# rev1.net
KiCad netlist of a schematic drawn in EAGLE
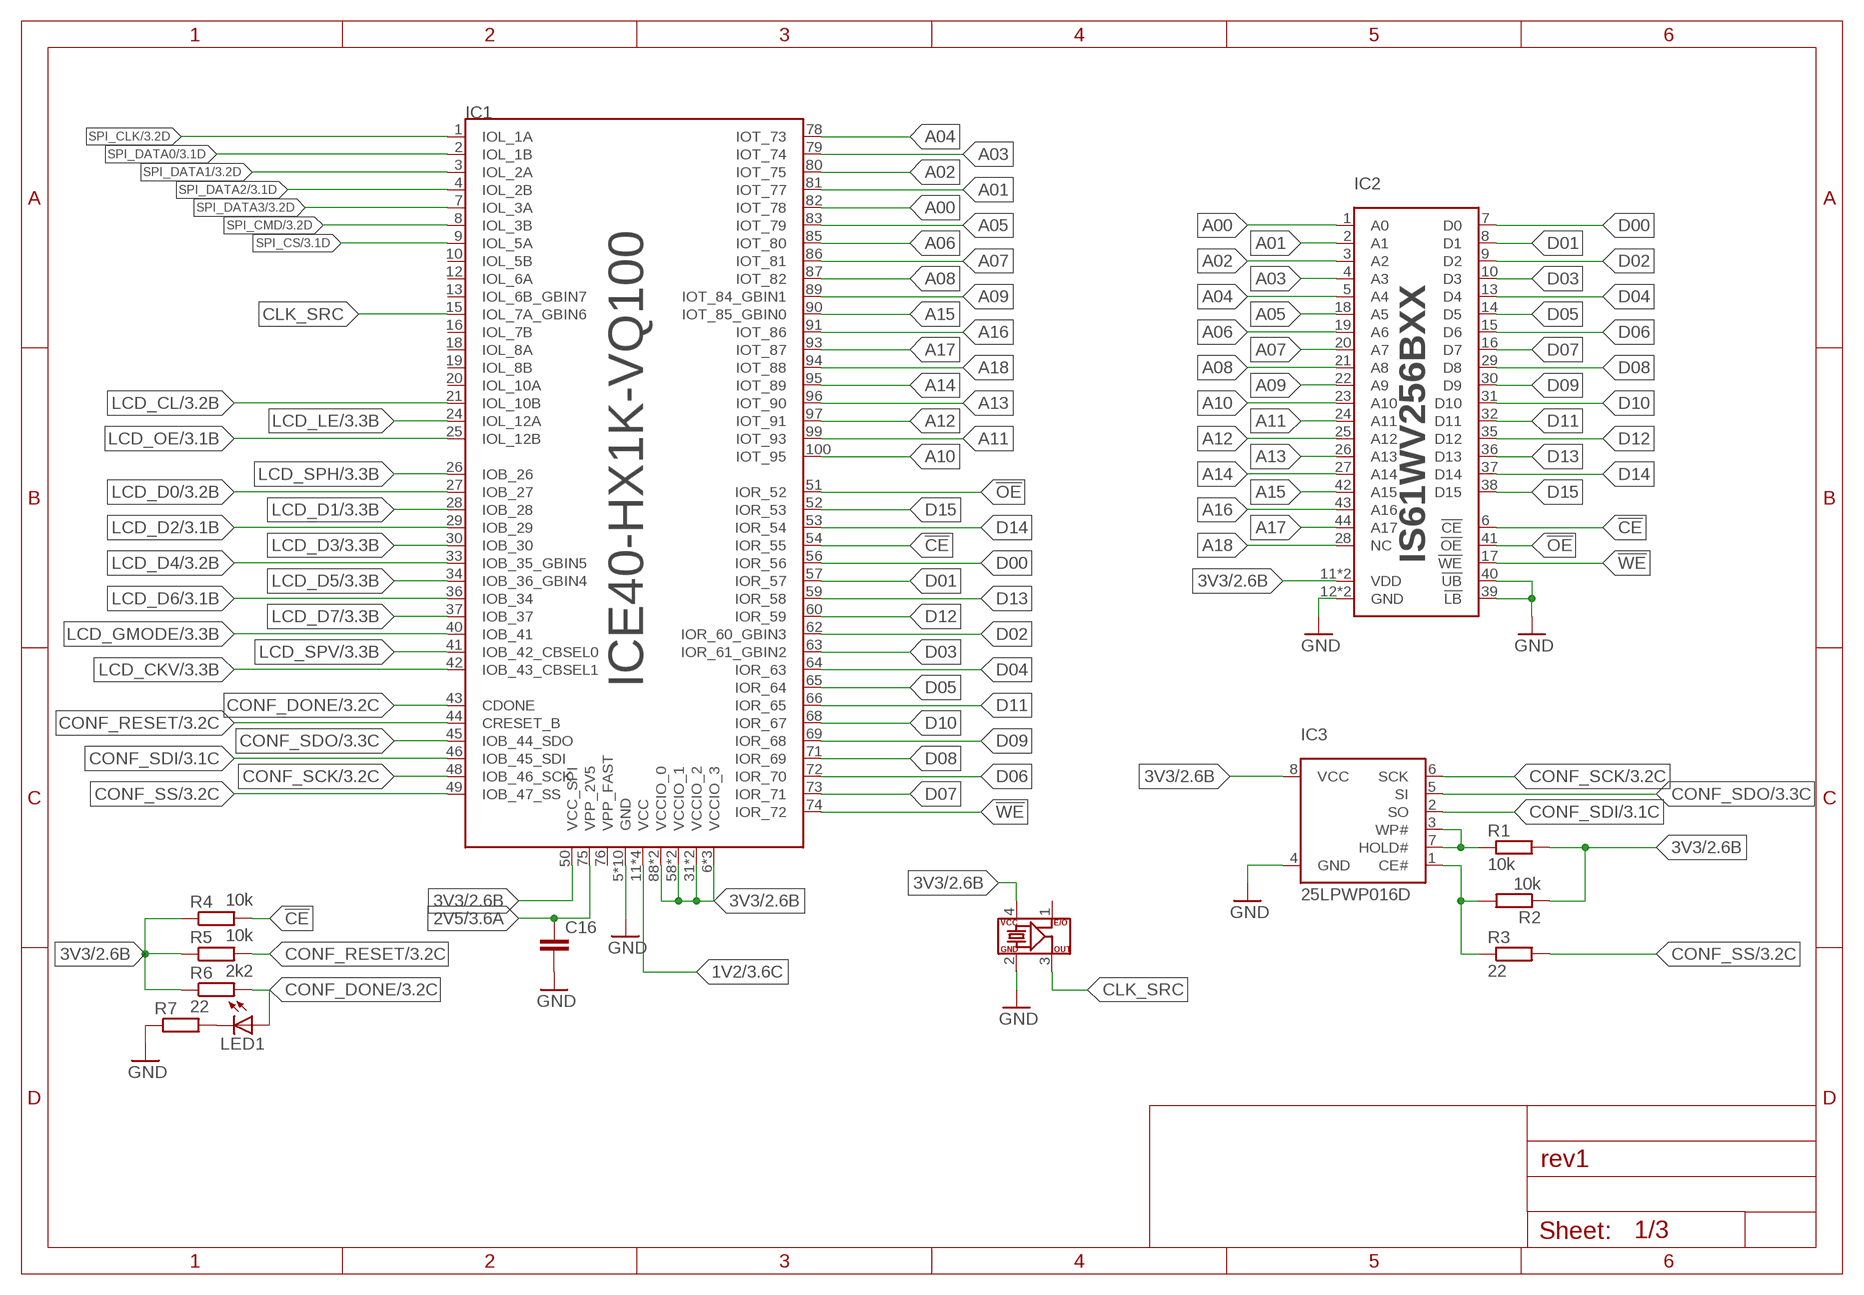
[diagram p0: schematic, sheet 1]
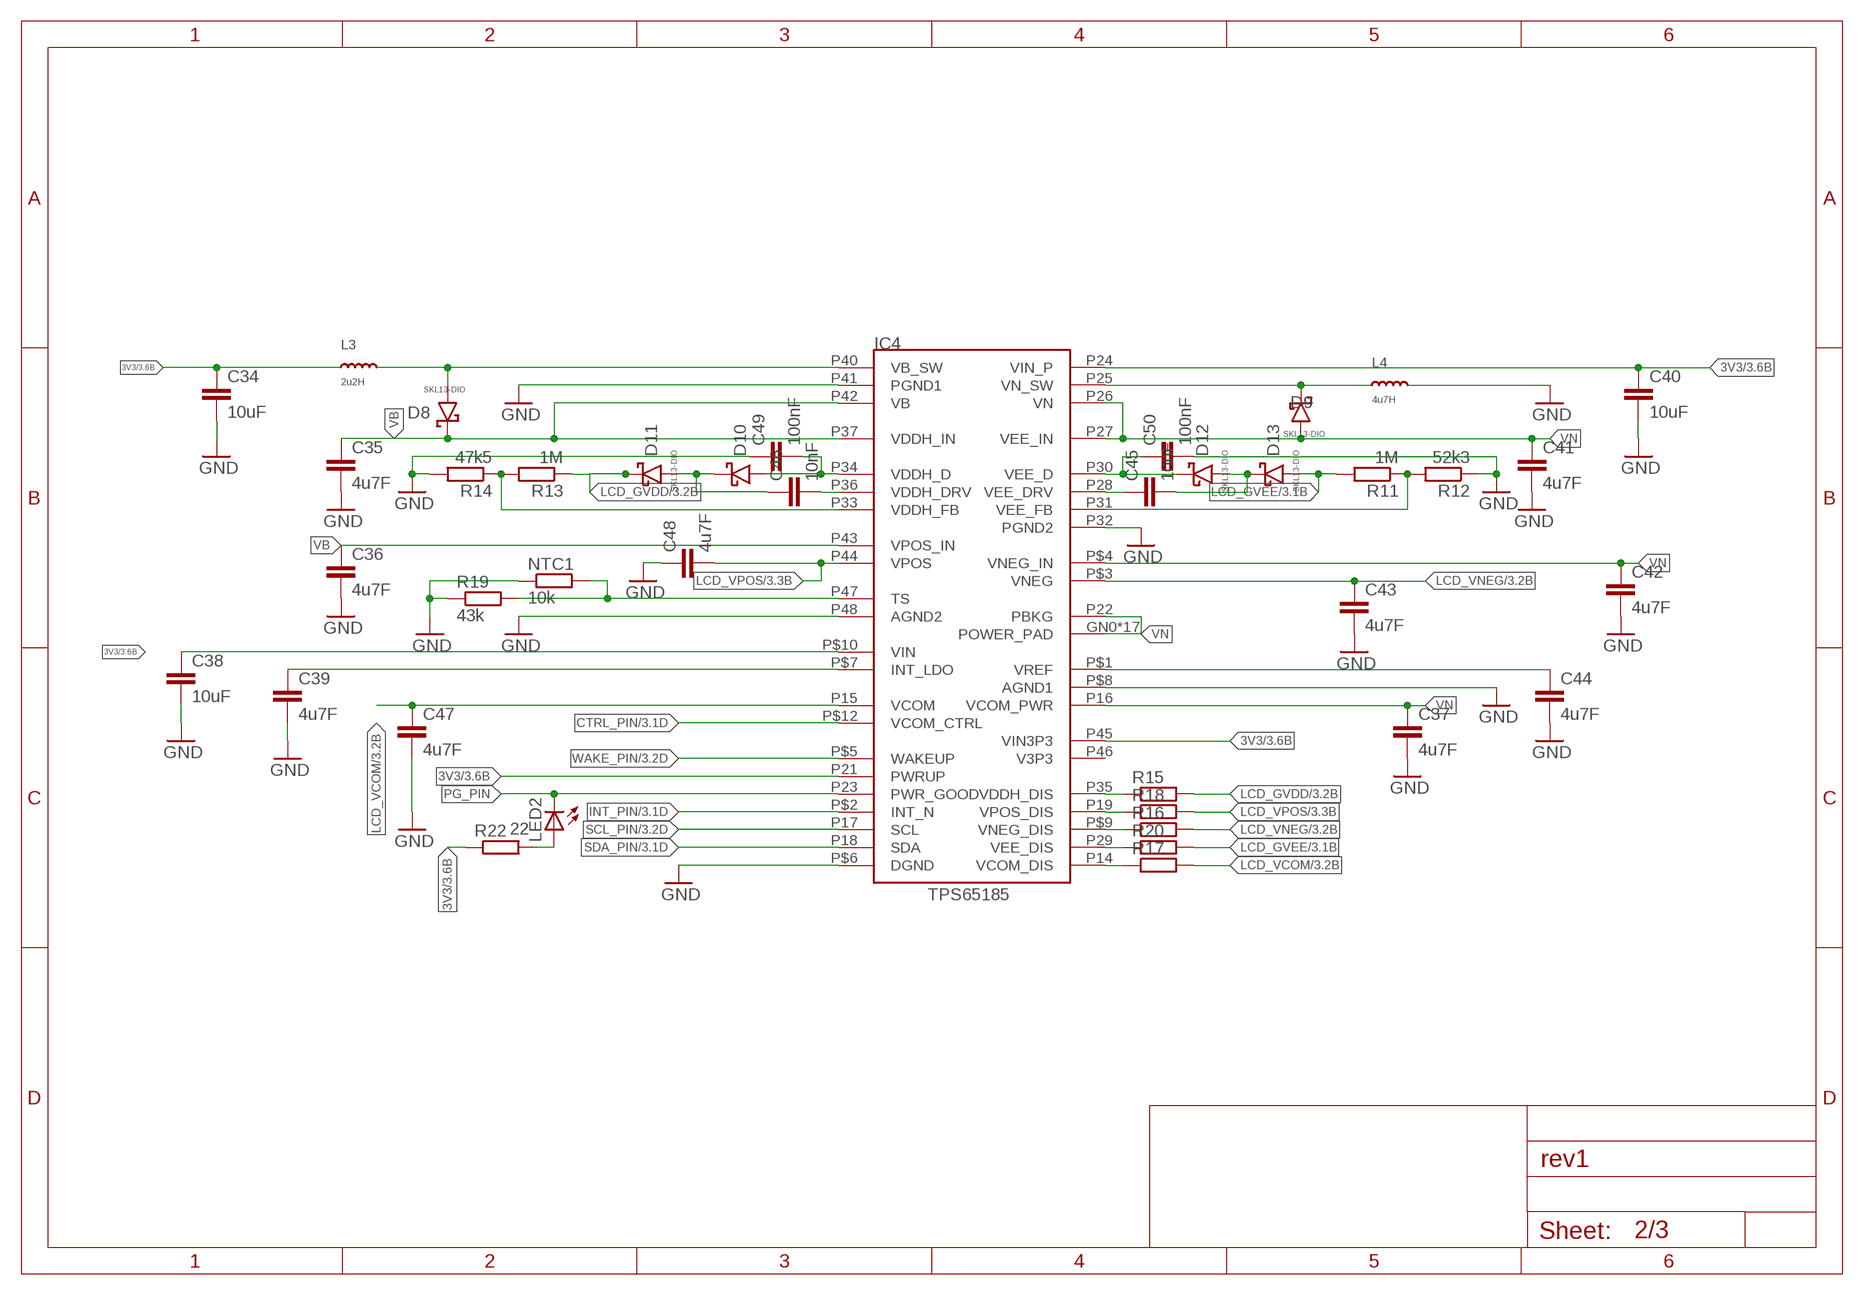
[diagram p1: schematic, sheet 2]
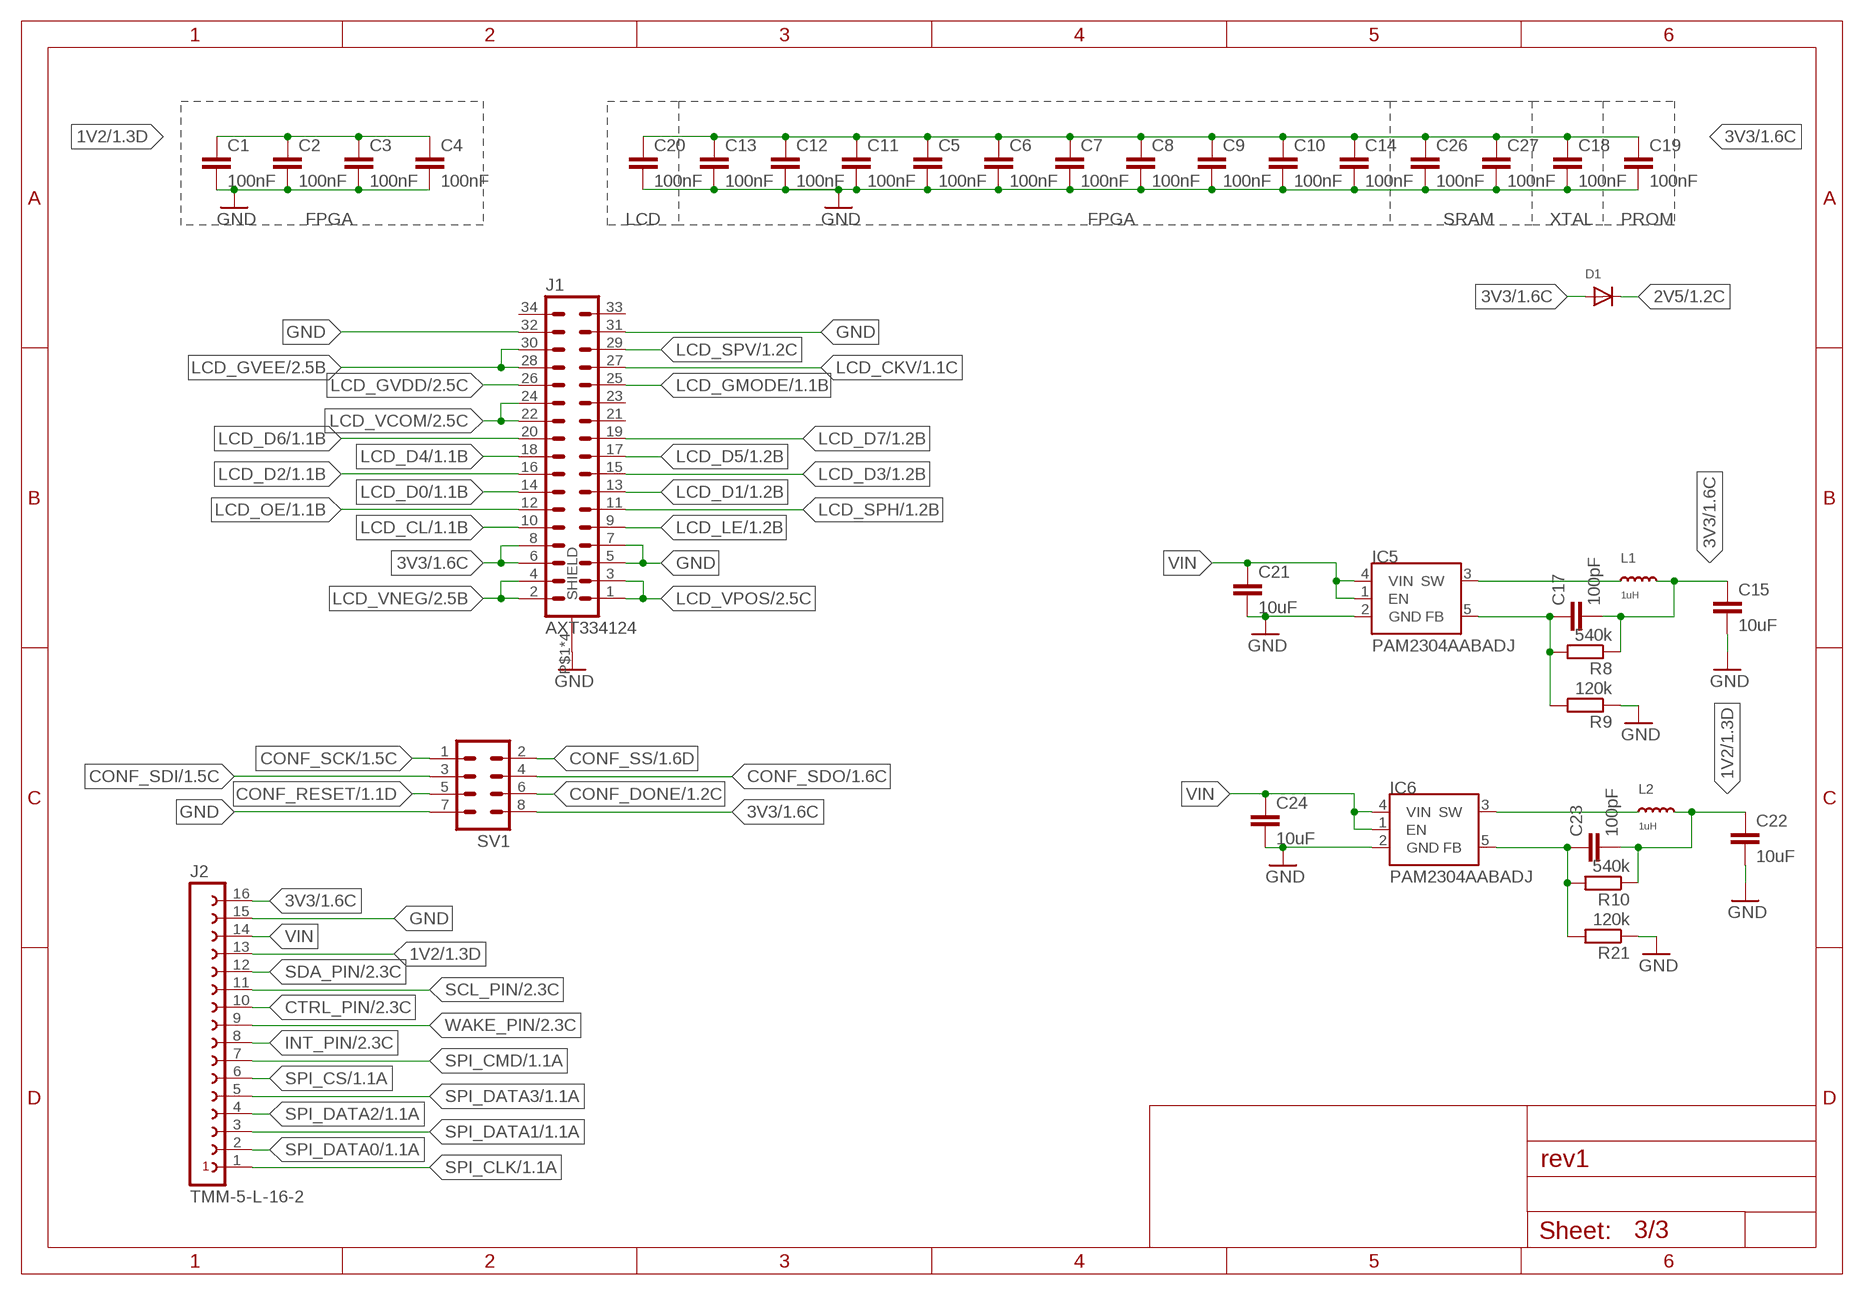
[diagram p2: schematic, sheet 3]

(export (version "E")
  (design (tool "Eeschema 10.0.6"))
  (components
    (comp (ref "C34")
      (value "10uF")
      (footprint "eagle-import:C0805")
      (libsource (lib "eagle-import") (part "C-EUC0805"))
    )
    (comp (ref "C35")
      (value "4u7F")
      (footprint "eagle-import:C0805")
      (libsource (lib "eagle-import") (part "C-EUC0805"))
    )
    (comp (ref "C36")
      (value "4u7F")
      (footprint "eagle-import:C0805")
      (libsource (lib "eagle-import") (part "C-EUC0805"))
    )
    (comp (ref "C37")
      (value "4u7F")
      (footprint "eagle-import:C0805")
      (libsource (lib "eagle-import") (part "C-EUC0805"))
    )
    (comp (ref "C38")
      (value "10uF")
      (footprint "eagle-import:C0805")
      (libsource (lib "eagle-import") (part "C-EUC0805"))
    )
    (comp (ref "C39")
      (value "4u7F")
      (footprint "eagle-import:C0603")
      (libsource (lib "eagle-import") (part "C-EUC0603"))
    )
    (comp (ref "C40")
      (value "10uF")
      (footprint "eagle-import:C0805")
      (libsource (lib "eagle-import") (part "C-EUC0805"))
    )
    (comp (ref "C41")
      (value "4u7F")
      (footprint "eagle-import:C0805")
      (libsource (lib "eagle-import") (part "C-EUC0805"))
    )
    (comp (ref "C42")
      (value "4u7F")
      (footprint "eagle-import:C0805")
      (libsource (lib "eagle-import") (part "C-EUC0805"))
    )
    (comp (ref "C43")
      (value "4u7F")
      (footprint "eagle-import:C0805")
      (libsource (lib "eagle-import") (part "C-EUC0805"))
    )
    (comp (ref "C44")
      (value "4u7F")
      (footprint "eagle-import:C0603")
      (libsource (lib "eagle-import") (part "C-EUC0603"))
    )
    (comp (ref "C45")
      (value "10nF")
      (footprint "eagle-import:C0402")
      (libsource (lib "eagle-import") (part "C-EUC0402"))
    )
    (comp (ref "C46")
      (value "10nF")
      (footprint "eagle-import:C0402")
      (libsource (lib "eagle-import") (part "C-EUC0402"))
    )
    (comp (ref "C47")
      (value "4u7F")
      (footprint "eagle-import:C0603")
      (libsource (lib "eagle-import") (part "C-EUC0603"))
    )
    (comp (ref "C48")
      (value "4u7F")
      (footprint "eagle-import:C0805")
      (libsource (lib "eagle-import") (part "C-EUC0805"))
    )
    (comp (ref "C49")
      (value "100nF")
      (footprint "eagle-import:C0402")
      (libsource (lib "eagle-import") (part "C-EUC0402"))
    )
    (comp (ref "C50")
      (value "100nF")
      (footprint "eagle-import:C0402")
      (libsource (lib "eagle-import") (part "C-EUC0402"))
    )
    (comp (ref "D8")
      (value "SKL13-DIO")
      (footprint "eagle-import:SOD523")
      (libsource (lib "eagle-import") (part "RB520S30T"))
    )
    (comp (ref "D9")
      (value "SKL13-DIO")
      (footprint "eagle-import:SOD523")
      (libsource (lib "eagle-import") (part "RB520S30T"))
    )
    (comp (ref "D10")
      (value "SKL13-DIO")
      (footprint "eagle-import:SOD523")
      (libsource (lib "eagle-import") (part "RB520S30T"))
    )
    (comp (ref "D11")
      (value "SKL13-DIO")
      (footprint "eagle-import:SOD523")
      (libsource (lib "eagle-import") (part "RB520S30T"))
    )
    (comp (ref "D12")
      (value "SKL13-DIO")
      (footprint "eagle-import:SOD523")
      (libsource (lib "eagle-import") (part "RB520S30T"))
    )
    (comp (ref "D13")
      (value "SKL13-DIO")
      (footprint "eagle-import:SOD523")
      (libsource (lib "eagle-import") (part "RB520S30T"))
    )
    (comp (ref "IC4")
      (value "TPS65185")
      (footprint "eagle-import:RGZ")
      (libsource (lib "eagle-import") (part "TPS65185"))
    )
    (comp (ref "L3")
      (value "2u2H")
      (footprint "eagle-import:3015")
      (libsource (lib "eagle-import") (part "DJNR-3015-2R2"))
    )
    (comp (ref "L4")
      (value "4u7H")
      (footprint "eagle-import:3015")
      (libsource (lib "eagle-import") (part "DJNR-3015-1R0"))
    )
    (comp (ref "LED2")
      (value "LEDCHIP-LED0603")
      (footprint "eagle-import:CHIP-LED0603")
      (libsource (lib "eagle-import") (part "LEDCHIP-LED0603"))
    )
    (comp (ref "NTC1")
      (value "10k")
      (footprint "eagle-import:R0603")
      (libsource (lib "eagle-import") (part "R-EU_R0603"))
    )
    (comp (ref "R11")
      (value "1M")
      (footprint "eagle-import:R0603")
      (libsource (lib "eagle-import") (part "R-EU_R0603"))
    )
    (comp (ref "R12")
      (value "52k3")
      (footprint "eagle-import:R0603")
      (libsource (lib "eagle-import") (part "R-EU_R0603"))
    )
    (comp (ref "R13")
      (value "1M")
      (footprint "eagle-import:R0603")
      (libsource (lib "eagle-import") (part "R-EU_R0603"))
    )
    (comp (ref "R14")
      (value "47k5")
      (footprint "eagle-import:R0603")
      (libsource (lib "eagle-import") (part "R-EU_R0603"))
    )
    (comp (ref "R15")
      (value "R-EU_R0603")
      (footprint "eagle-import:R0603")
      (libsource (lib "eagle-import") (part "R-EU_R0603"))
    )
    (comp (ref "R16")
      (value "R-EU_R0603")
      (footprint "eagle-import:R0603")
      (libsource (lib "eagle-import") (part "R-EU_R0603"))
    )
    (comp (ref "R17")
      (value "R-EU_R0603")
      (footprint "eagle-import:R0603")
      (libsource (lib "eagle-import") (part "R-EU_R0603"))
    )
    (comp (ref "R18")
      (value "R-EU_R0603")
      (footprint "eagle-import:R0603")
      (libsource (lib "eagle-import") (part "R-EU_R0603"))
    )
    (comp (ref "R19")
      (value "43k")
      (footprint "eagle-import:R0603")
      (libsource (lib "eagle-import") (part "R-EU_R0603"))
    )
    (comp (ref "R20")
      (value "R-EU_R0603")
      (footprint "eagle-import:R0603")
      (libsource (lib "eagle-import") (part "R-EU_R0603"))
    )
    (comp (ref "R22")
      (value "22")
      (footprint "eagle-import:R0402")
      (libsource (lib "eagle-import") (part "R-EU_R0402"))
    )
    (comp (ref "C1")
      (value "100nF")
      (footprint "eagle-import:C0402")
      (libsource (lib "eagle-import") (part "C-EUC0402"))
    )
    (comp (ref "C2")
      (value "100nF")
      (footprint "eagle-import:C0402")
      (libsource (lib "eagle-import") (part "C-EUC0402"))
    )
    (comp (ref "C3")
      (value "100nF")
      (footprint "eagle-import:C0402")
      (libsource (lib "eagle-import") (part "C-EUC0402"))
    )
    (comp (ref "C4")
      (value "100nF")
      (footprint "eagle-import:C0402")
      (libsource (lib "eagle-import") (part "C-EUC0402"))
    )
    (comp (ref "C5")
      (value "100nF")
      (footprint "eagle-import:C0402")
      (libsource (lib "eagle-import") (part "C-EUC0402"))
    )
    (comp (ref "C6")
      (value "100nF")
      (footprint "eagle-import:C0402")
      (libsource (lib "eagle-import") (part "C-EUC0402"))
    )
    (comp (ref "C7")
      (value "100nF")
      (footprint "eagle-import:C0402")
      (libsource (lib "eagle-import") (part "C-EUC0402"))
    )
    (comp (ref "C8")
      (value "100nF")
      (footprint "eagle-import:C0402")
      (libsource (lib "eagle-import") (part "C-EUC0402"))
    )
    (comp (ref "C9")
      (value "100nF")
      (footprint "eagle-import:C0402")
      (libsource (lib "eagle-import") (part "C-EUC0402"))
    )
    (comp (ref "C10")
      (value "100nF")
      (footprint "eagle-import:C0402")
      (libsource (lib "eagle-import") (part "C-EUC0402"))
    )
    (comp (ref "C11")
      (value "100nF")
      (footprint "eagle-import:C0402")
      (libsource (lib "eagle-import") (part "C-EUC0402"))
    )
    (comp (ref "C12")
      (value "100nF")
      (footprint "eagle-import:C0402")
      (libsource (lib "eagle-import") (part "C-EUC0402"))
    )
    (comp (ref "C13")
      (value "100nF")
      (footprint "eagle-import:C0402")
      (libsource (lib "eagle-import") (part "C-EUC0402"))
    )
    (comp (ref "C14")
      (value "100nF")
      (footprint "eagle-import:C0402")
      (libsource (lib "eagle-import") (part "C-EUC0402"))
    )
    (comp (ref "C15")
      (value "10uF")
      (footprint "eagle-import:C0603")
      (libsource (lib "eagle-import") (part "C-EUC0603"))
    )
    (comp (ref "C17")
      (value "100pF")
      (footprint "eagle-import:C0402")
      (libsource (lib "eagle-import") (part "C-EUC0402"))
    )
    (comp (ref "C18")
      (value "100nF")
      (footprint "eagle-import:C0402")
      (libsource (lib "eagle-import") (part "C-EUC0402"))
    )
    (comp (ref "C19")
      (value "100nF")
      (footprint "eagle-import:C0402")
      (libsource (lib "eagle-import") (part "C-EUC0402"))
    )
    (comp (ref "C20")
      (value "100nF")
      (footprint "eagle-import:C0402")
      (libsource (lib "eagle-import") (part "C-EUC0402"))
    )
    (comp (ref "C21")
      (value "10uF")
      (footprint "eagle-import:C0603")
      (libsource (lib "eagle-import") (part "C-EUC0603"))
    )
    (comp (ref "C22")
      (value "10uF")
      (footprint "eagle-import:C0603")
      (libsource (lib "eagle-import") (part "C-EUC0603"))
    )
    (comp (ref "C23")
      (value "100pF")
      (footprint "eagle-import:C0402")
      (libsource (lib "eagle-import") (part "C-EUC0402"))
    )
    (comp (ref "C24")
      (value "10uF")
      (footprint "eagle-import:C0603")
      (libsource (lib "eagle-import") (part "C-EUC0603"))
    )
    (comp (ref "C26")
      (value "100nF")
      (footprint "eagle-import:C0402")
      (libsource (lib "eagle-import") (part "C-EUC0402"))
    )
    (comp (ref "C27")
      (value "100nF")
      (footprint "eagle-import:C0402")
      (libsource (lib "eagle-import") (part "C-EUC0402"))
    )
    (comp (ref "D1")
      (value "DIODESOD-123")
      (footprint "eagle-import:SOD-123")
      (libsource (lib "eagle-import") (part "DIODESOD-123"))
    )
    (comp (ref "IC5")
      (value "PAM2304AABADJ")
      (footprint "eagle-import:TSOT25")
      (libsource (lib "eagle-import") (part "PAM2304AABADJ"))
    )
    (comp (ref "IC6")
      (value "PAM2304AABADJ")
      (footprint "eagle-import:TSOT25")
      (libsource (lib "eagle-import") (part "PAM2304AABADJ"))
    )
    (comp (ref "J1")
      (value "AXT334124")
      (footprint "eagle-import:AXT334124")
      (libsource (lib "eagle-import") (part "AXT334124"))
    )
    (comp (ref "J2")
      (value "TMM-5-L-16-2")
      (footprint "eagle-import:TMM-5-L-16-2")
      (libsource (lib "eagle-import") (part "TMM-5-L-16-2"))
    )
    (comp (ref "L1")
      (value "1uH")
      (footprint "eagle-import:3015")
      (libsource (lib "eagle-import") (part "DJNR-3015-1R0"))
    )
    (comp (ref "L2")
      (value "1uH")
      (footprint "eagle-import:3015")
      (libsource (lib "eagle-import") (part "DJNR-3015-1R0"))
    )
    (comp (ref "R8")
      (value "540k")
      (footprint "eagle-import:R0402")
      (libsource (lib "eagle-import") (part "R-EU_R0402"))
    )
    (comp (ref "R9")
      (value "120k")
      (footprint "eagle-import:R0402")
      (libsource (lib "eagle-import") (part "R-EU_R0402"))
    )
    (comp (ref "R10")
      (value "540k")
      (footprint "eagle-import:R0402")
      (libsource (lib "eagle-import") (part "R-EU_R0402"))
    )
    (comp (ref "R21")
      (value "120k")
      (footprint "eagle-import:R0402")
      (libsource (lib "eagle-import") (part "R-EU_R0402"))
    )
    (comp (ref "SV1")
      (value "MA04-2")
      (footprint "eagle-import:MA04-2")
      (libsource (lib "eagle-import") (part "MA04-2"))
    )
    (comp (ref "C16")
      (value "C-EUC0402")
      (footprint "eagle-import:C0402")
      (libsource (lib "eagle-import") (part "C-EUC0402"))
    )
    (comp (ref "IC1")
      (value "ICE40-HX1K-VQ100")
      (footprint "eagle-import:VQ100")
      (libsource (lib "eagle-import") (part "ICE40-HX1K-VQ100"))
    )
    (comp (ref "IC2")
      (value "IS61WV256BXX")
      (footprint "eagle-import:TSOP-2")
      (libsource (lib "eagle-import") (part "IS61WV256BXX"))
    )
    (comp (ref "IC3")
      (value "25LPWP016D")
      (footprint "eagle-import:SOP08")
      (libsource (lib "eagle-import") (part "25LPWP016D"))
    )
    (comp (ref "LED1")
      (value "LEDCHIP-LED0603")
      (footprint "eagle-import:CHIP-LED0603")
      (libsource (lib "eagle-import") (part "LEDCHIP-LED0603"))
    )
    (comp (ref "R1")
      (value "10k")
      (footprint "eagle-import:R0402")
      (libsource (lib "eagle-import") (part "R-EU_R0402"))
    )
    (comp (ref "R2")
      (value "10k")
      (footprint "eagle-import:R0603")
      (libsource (lib "eagle-import") (part "R-EU_R0603"))
    )
    (comp (ref "R3")
      (value "22")
      (footprint "eagle-import:R0402")
      (libsource (lib "eagle-import") (part "R-EU_R0402"))
    )
    (comp (ref "R4")
      (value "10k")
      (footprint "eagle-import:R0402")
      (libsource (lib "eagle-import") (part "R-EU_R0402"))
    )
    (comp (ref "R5")
      (value "10k")
      (footprint "eagle-import:R0402")
      (libsource (lib "eagle-import") (part "R-EU_R0402"))
    )
    (comp (ref "R6")
      (value "2k2")
      (footprint "eagle-import:R0402")
      (libsource (lib "eagle-import") (part "R-EU_R0402"))
    )
    (comp (ref "R7")
      (value "22")
      (footprint "eagle-import:R0402")
      (libsource (lib "eagle-import") (part "R-EU_R0402"))
    )
    (comp (ref "X1")
      (value "DSC61XX")
      (footprint "eagle-import:3225")
      (libsource (lib "eagle-import") (part "DSC61XX"))
    )
  )
  (nets
    (net (code "1") (name "1V2") (class "Default")
      (node (ref "C1") (pin "1") (pinfunction "1_1") (pintype "passive"))
      (node (ref "C2") (pin "1") (pinfunction "1_1") (pintype "passive"))
      (node (ref "C22") (pin "1") (pinfunction "1_1") (pintype "passive"))
      (node (ref "C23") (pin "2") (pinfunction "2_2") (pintype "passive"))
      (node (ref "C3") (pin "1") (pinfunction "1_1") (pintype "passive"))
      (node (ref "C4") (pin "1") (pinfunction "1_1") (pintype "passive"))
      (node (ref "IC1") (pin "11") (pinfunction "VCC_11") (pintype "bidirectional"))
      (node (ref "IC1") (pin "35") (pinfunction "VCC_35") (pintype "bidirectional"))
      (node (ref "IC1") (pin "61") (pinfunction "VCC_61") (pintype "bidirectional"))
      (node (ref "IC1") (pin "77") (pinfunction "VCC_77") (pintype "bidirectional"))
      (node (ref "J2") (pin "13") (pinfunction "13_13") (pintype "passive"))
      (node (ref "L2") (pin "P$2") (pinfunction "P$2_P$2") (pintype "bidirectional"))
      (node (ref "R10") (pin "1") (pinfunction "1_1") (pintype "passive"))
    )
    (net (code "2") (name "2V5") (class "Default")
      (node (ref "C16") (pin "1") (pinfunction "1_1") (pintype "passive"))
      (node (ref "D1") (pin "C") (pinfunction "C_C") (pintype "passive"))
      (node (ref "IC1") (pin "75") (pinfunction "VPP_2V5_75") (pintype "bidirectional"))
    )
    (net (code "3") (name "3V3") (class "Default")
      (node (ref "C10") (pin "1") (pinfunction "1_1") (pintype "passive"))
      (node (ref "C11") (pin "1") (pinfunction "1_1") (pintype "passive"))
      (node (ref "C12") (pin "1") (pinfunction "1_1") (pintype "passive"))
      (node (ref "C13") (pin "1") (pinfunction "1_1") (pintype "passive"))
      (node (ref "C14") (pin "1") (pinfunction "1_1") (pintype "passive"))
      (node (ref "C15") (pin "1") (pinfunction "1_1") (pintype "passive"))
      (node (ref "C17") (pin "2") (pinfunction "2_2") (pintype "passive"))
      (node (ref "C18") (pin "1") (pinfunction "1_1") (pintype "passive"))
      (node (ref "C19") (pin "1") (pinfunction "1_1") (pintype "passive"))
      (node (ref "C20") (pin "1") (pinfunction "1_1") (pintype "passive"))
      (node (ref "C26") (pin "1") (pinfunction "1_1") (pintype "passive"))
      (node (ref "C27") (pin "1") (pinfunction "1_1") (pintype "passive"))
      (node (ref "C34") (pin "1") (pinfunction "1_1") (pintype "passive"))
      (node (ref "C38") (pin "1") (pinfunction "1_1") (pintype "passive"))
      (node (ref "C40") (pin "1") (pinfunction "1_1") (pintype "passive"))
      (node (ref "C5") (pin "1") (pinfunction "1_1") (pintype "passive"))
      (node (ref "C6") (pin "1") (pinfunction "1_1") (pintype "passive"))
      (node (ref "C7") (pin "1") (pinfunction "1_1") (pintype "passive"))
      (node (ref "C8") (pin "1") (pinfunction "1_1") (pintype "passive"))
      (node (ref "C9") (pin "1") (pinfunction "1_1") (pintype "passive"))
      (node (ref "D1") (pin "A") (pinfunction "A_A") (pintype "passive"))
      (node (ref "IC1") (pin "14") (pinfunction "VCCIO_3_14") (pintype "bidirectional"))
      (node (ref "IC1") (pin "22") (pinfunction "VCCIO_3_22") (pintype "bidirectional"))
      (node (ref "IC1") (pin "31") (pinfunction "VCCIO_2_31") (pintype "bidirectional"))
      (node (ref "IC1") (pin "38") (pinfunction "VCCIO_2_38") (pintype "bidirectional"))
      (node (ref "IC1") (pin "50") (pinfunction "VCC_SPI_50") (pintype "bidirectional"))
      (node (ref "IC1") (pin "58") (pinfunction "VCCIO_1_58") (pintype "bidirectional"))
      (node (ref "IC1") (pin "6") (pinfunction "VCCIO_3_6") (pintype "bidirectional"))
      (node (ref "IC1") (pin "67") (pinfunction "VCCIO_1_67") (pintype "bidirectional"))
      (node (ref "IC1") (pin "88") (pinfunction "VCCIO_0_88") (pintype "bidirectional"))
      (node (ref "IC1") (pin "92") (pinfunction "VCCIO_0_92") (pintype "bidirectional"))
      (node (ref "IC2") (pin "11") (pinfunction "VDD_11") (pintype "bidirectional"))
      (node (ref "IC2") (pin "33") (pinfunction "VDD_33") (pintype "bidirectional"))
      (node (ref "IC3") (pin "8") (pinfunction "VCC_8") (pintype "bidirectional"))
      (node (ref "IC4") (pin "P$10") (pinfunction "VIN_P$10") (pintype "bidirectional"))
      (node (ref "IC4") (pin "P21") (pinfunction "PWRUP_P21") (pintype "bidirectional"))
      (node (ref "IC4") (pin "P24") (pinfunction "VIN_P_P24") (pintype "bidirectional"))
      (node (ref "IC4") (pin "P45") (pinfunction "VIN3P3_P45") (pintype "bidirectional"))
      (node (ref "J1") (pin "6") (pinfunction "6_6") (pintype "passive"))
      (node (ref "J1") (pin "8") (pinfunction "8_8") (pintype "passive"))
      (node (ref "J2") (pin "16") (pinfunction "16_16") (pintype "passive"))
      (node (ref "L1") (pin "P$2") (pinfunction "P$2_P$2") (pintype "bidirectional"))
      (node (ref "L3") (pin "P$1") (pinfunction "P$1_P$1") (pintype "bidirectional"))
      (node (ref "R1") (pin "2") (pinfunction "2_2") (pintype "passive"))
      (node (ref "R2") (pin "1") (pinfunction "1_1") (pintype "passive"))
      (node (ref "R22") (pin "1") (pinfunction "1_1") (pintype "passive"))
      (node (ref "R4") (pin "1") (pinfunction "1_1") (pintype "passive"))
      (node (ref "R5") (pin "1") (pinfunction "1_1") (pintype "passive"))
      (node (ref "R6") (pin "1") (pinfunction "1_1") (pintype "passive"))
      (node (ref "R8") (pin "1") (pinfunction "1_1") (pintype "passive"))
      (node (ref "SV1") (pin "8") (pinfunction "8_8") (pintype "passive"))
      (node (ref "X1") (pin "4") (pinfunction "4_4") (pintype "bidirectional"))
    )
    (net (code "4") (name "A00") (class "Default")
      (node (ref "IC1") (pin "82") (pinfunction "IOT_78_82") (pintype "bidirectional"))
      (node (ref "IC2") (pin "1") (pinfunction "A0_1") (pintype "bidirectional"))
    )
    (net (code "5") (name "A01") (class "Default")
      (node (ref "IC1") (pin "81") (pinfunction "IOT_77_81") (pintype "bidirectional"))
      (node (ref "IC2") (pin "2") (pinfunction "A1_2") (pintype "bidirectional"))
    )
    (net (code "6") (name "A02") (class "Default")
      (node (ref "IC1") (pin "80") (pinfunction "IOT_75_80") (pintype "bidirectional"))
      (node (ref "IC2") (pin "3") (pinfunction "A2_3") (pintype "bidirectional"))
    )
    (net (code "7") (name "A03") (class "Default")
      (node (ref "IC1") (pin "79") (pinfunction "IOT_74_79") (pintype "bidirectional"))
      (node (ref "IC2") (pin "4") (pinfunction "A3_4") (pintype "bidirectional"))
    )
    (net (code "8") (name "A04") (class "Default")
      (node (ref "IC1") (pin "78") (pinfunction "IOT_73_78") (pintype "bidirectional"))
      (node (ref "IC2") (pin "5") (pinfunction "A4_5") (pintype "bidirectional"))
    )
    (net (code "9") (name "A05") (class "Default")
      (node (ref "IC1") (pin "83") (pinfunction "IOT_79_83") (pintype "bidirectional"))
      (node (ref "IC2") (pin "18") (pinfunction "A5_18") (pintype "bidirectional"))
    )
    (net (code "10") (name "A06") (class "Default")
      (node (ref "IC1") (pin "85") (pinfunction "IOT_80_85") (pintype "bidirectional"))
      (node (ref "IC2") (pin "19") (pinfunction "A6_19") (pintype "bidirectional"))
    )
    (net (code "11") (name "A07") (class "Default")
      (node (ref "IC1") (pin "86") (pinfunction "IOT_81_86") (pintype "bidirectional"))
      (node (ref "IC2") (pin "20") (pinfunction "A7_20") (pintype "bidirectional"))
    )
    (net (code "12") (name "A08") (class "Default")
      (node (ref "IC1") (pin "87") (pinfunction "IOT_82_87") (pintype "bidirectional"))
      (node (ref "IC2") (pin "21") (pinfunction "A8_21") (pintype "bidirectional"))
    )
    (net (code "13") (name "A09") (class "Default")
      (node (ref "IC1") (pin "89") (pinfunction "IOT_84_GBIN1_89") (pintype "bidirectional"))
      (node (ref "IC2") (pin "22") (pinfunction "A9_22") (pintype "bidirectional"))
    )
    (net (code "14") (name "A10") (class "Default")
      (node (ref "IC1") (pin "100") (pinfunction "IOT_95_100") (pintype "bidirectional"))
      (node (ref "IC2") (pin "23") (pinfunction "A10_23") (pintype "bidirectional"))
    )
    (net (code "15") (name "A11") (class "Default")
      (node (ref "IC1") (pin "99") (pinfunction "IOT_93_99") (pintype "bidirectional"))
      (node (ref "IC2") (pin "24") (pinfunction "A11_24") (pintype "bidirectional"))
    )
    (net (code "16") (name "A12") (class "Default")
      (node (ref "IC1") (pin "97") (pinfunction "IOT_91_97") (pintype "bidirectional"))
      (node (ref "IC2") (pin "25") (pinfunction "A12_25") (pintype "bidirectional"))
    )
    (net (code "17") (name "A13") (class "Default")
      (node (ref "IC1") (pin "96") (pinfunction "IOT_90_96") (pintype "bidirectional"))
      (node (ref "IC2") (pin "26") (pinfunction "A13_26") (pintype "bidirectional"))
    )
    (net (code "18") (name "A14") (class "Default")
      (node (ref "IC1") (pin "95") (pinfunction "IOT_89_95") (pintype "bidirectional"))
      (node (ref "IC2") (pin "27") (pinfunction "A14_27") (pintype "bidirectional"))
    )
    (net (code "19") (name "A15") (class "Default")
      (node (ref "IC1") (pin "90") (pinfunction "IOT_85_GBIN0_90") (pintype "bidirectional"))
      (node (ref "IC2") (pin "42") (pinfunction "A15_42") (pintype "bidirectional"))
    )
    (net (code "20") (name "A16") (class "Default")
      (node (ref "IC1") (pin "91") (pinfunction "IOT_86_91") (pintype "bidirectional"))
      (node (ref "IC2") (pin "43") (pinfunction "A16_43") (pintype "bidirectional"))
    )
    (net (code "21") (name "A17") (class "Default")
      (node (ref "IC1") (pin "93") (pinfunction "IOT_87_93") (pintype "bidirectional"))
      (node (ref "IC2") (pin "44") (pinfunction "A17_44") (pintype "bidirectional"))
    )
    (net (code "22") (name "A18") (class "Default")
      (node (ref "IC1") (pin "94") (pinfunction "IOT_88_94") (pintype "bidirectional"))
      (node (ref "IC2") (pin "28") (pinfunction "NC_28") (pintype "bidirectional"))
    )
    (net (code "23") (name "CLK_SRC") (class "Default")
      (node (ref "IC1") (pin "15") (pinfunction "IOL_7A_GBIN6_15") (pintype "bidirectional"))
      (node (ref "X1") (pin "3") (pinfunction "3_3") (pintype "bidirectional"))
    )
    (net (code "24") (name "CONF_DONE") (class "Default")
      (node (ref "IC1") (pin "43") (pinfunction "CDONE_43") (pintype "bidirectional"))
      (node (ref "LED1") (pin "A") (pinfunction "A_A") (pintype "passive"))
      (node (ref "R6") (pin "2") (pinfunction "2_2") (pintype "passive"))
      (node (ref "SV1") (pin "6") (pinfunction "6_6") (pintype "passive"))
    )
    (net (code "25") (name "CONF_RESET") (class "Default")
      (node (ref "IC1") (pin "44") (pinfunction "CRESET_B_44") (pintype "bidirectional"))
      (node (ref "R5") (pin "2") (pinfunction "2_2") (pintype "passive"))
      (node (ref "SV1") (pin "5") (pinfunction "5_5") (pintype "passive"))
    )
    (net (code "26") (name "CONF_SCK") (class "Default")
      (node (ref "IC1") (pin "48") (pinfunction "IOB_46_SCK_48") (pintype "bidirectional"))
      (node (ref "IC3") (pin "6") (pinfunction "SCK_6") (pintype "bidirectional"))
      (node (ref "SV1") (pin "1") (pinfunction "1_1") (pintype "passive"))
    )
    (net (code "27") (name "CONF_SDI") (class "Default")
      (node (ref "IC1") (pin "46") (pinfunction "IOB_45_SDI_46") (pintype "bidirectional"))
      (node (ref "IC3") (pin "2") (pinfunction "SO_2") (pintype "bidirectional"))
      (node (ref "SV1") (pin "3") (pinfunction "3_3") (pintype "passive"))
    )
    (net (code "28") (name "CONF_SDO") (class "Default")
      (node (ref "IC1") (pin "45") (pinfunction "IOB_44_SDO_45") (pintype "bidirectional"))
      (node (ref "IC3") (pin "5") (pinfunction "SI_5") (pintype "bidirectional"))
      (node (ref "SV1") (pin "4") (pinfunction "4_4") (pintype "passive"))
    )
    (net (code "29") (name "CONF_SS") (class "Default")
      (node (ref "IC1") (pin "49") (pinfunction "IOB_47_SS_49") (pintype "bidirectional"))
      (node (ref "R3") (pin "2") (pinfunction "2_2") (pintype "passive"))
      (node (ref "SV1") (pin "2") (pinfunction "2_2") (pintype "passive"))
    )
    (net (code "30") (name "CTRL_PIN") (class "Default")
      (node (ref "IC4") (pin "P$12") (pinfunction "VCOM_CTRL_P$12") (pintype "bidirectional"))
      (node (ref "J2") (pin "10") (pinfunction "10_10") (pintype "passive"))
    )
    (net (code "31") (name "D00") (class "Default")
      (node (ref "IC1") (pin "56") (pinfunction "IOR_56_56") (pintype "bidirectional"))
      (node (ref "IC2") (pin "7") (pinfunction "D0_7") (pintype "bidirectional"))
    )
    (net (code "32") (name "D01") (class "Default")
      (node (ref "IC1") (pin "57") (pinfunction "IOR_57_57") (pintype "bidirectional"))
      (node (ref "IC2") (pin "8") (pinfunction "D1_8") (pintype "bidirectional"))
    )
    (net (code "33") (name "D02") (class "Default")
      (node (ref "IC1") (pin "62") (pinfunction "IOR_60_GBIN3_62") (pintype "bidirectional"))
      (node (ref "IC2") (pin "9") (pinfunction "D2_9") (pintype "bidirectional"))
    )
    (net (code "34") (name "D03") (class "Default")
      (node (ref "IC1") (pin "63") (pinfunction "IOR_61_GBIN2_63") (pintype "bidirectional"))
      (node (ref "IC2") (pin "10") (pinfunction "D3_10") (pintype "bidirectional"))
    )
    (net (code "35") (name "D04") (class "Default")
      (node (ref "IC1") (pin "64") (pinfunction "IOR_63_64") (pintype "bidirectional"))
      (node (ref "IC2") (pin "13") (pinfunction "D4_13") (pintype "bidirectional"))
    )
    (net (code "36") (name "D05") (class "Default")
      (node (ref "IC1") (pin "65") (pinfunction "IOR_64_65") (pintype "bidirectional"))
      (node (ref "IC2") (pin "14") (pinfunction "D5_14") (pintype "bidirectional"))
    )
    (net (code "37") (name "D06") (class "Default")
      (node (ref "IC1") (pin "72") (pinfunction "IOR_70_72") (pintype "bidirectional"))
      (node (ref "IC2") (pin "15") (pinfunction "D6_15") (pintype "bidirectional"))
    )
    (net (code "38") (name "D07") (class "Default")
      (node (ref "IC1") (pin "73") (pinfunction "IOR_71_73") (pintype "bidirectional"))
      (node (ref "IC2") (pin "16") (pinfunction "D7_16") (pintype "bidirectional"))
    )
    (net (code "39") (name "D08") (class "Default")
      (node (ref "IC1") (pin "71") (pinfunction "IOR_69_71") (pintype "bidirectional"))
      (node (ref "IC2") (pin "29") (pinfunction "D8_29") (pintype "bidirectional"))
    )
    (net (code "40") (name "D09") (class "Default")
      (node (ref "IC1") (pin "69") (pinfunction "IOR_68_69") (pintype "bidirectional"))
      (node (ref "IC2") (pin "30") (pinfunction "D9_30") (pintype "bidirectional"))
    )
    (net (code "41") (name "D10") (class "Default")
      (node (ref "IC1") (pin "68") (pinfunction "IOR_67_68") (pintype "bidirectional"))
      (node (ref "IC2") (pin "31") (pinfunction "D10_31") (pintype "bidirectional"))
    )
    (net (code "42") (name "D11") (class "Default")
      (node (ref "IC1") (pin "66") (pinfunction "IOR_65_66") (pintype "bidirectional"))
      (node (ref "IC2") (pin "32") (pinfunction "D11_32") (pintype "bidirectional"))
    )
    (net (code "43") (name "D12") (class "Default")
      (node (ref "IC1") (pin "60") (pinfunction "IOR_59_60") (pintype "bidirectional"))
      (node (ref "IC2") (pin "35") (pinfunction "D12_35") (pintype "bidirectional"))
    )
    (net (code "44") (name "D13") (class "Default")
      (node (ref "IC1") (pin "59") (pinfunction "IOR_58_59") (pintype "bidirectional"))
      (node (ref "IC2") (pin "36") (pinfunction "D13_36") (pintype "bidirectional"))
    )
    (net (code "45") (name "D14") (class "Default")
      (node (ref "IC1") (pin "53") (pinfunction "IOR_54_53") (pintype "bidirectional"))
      (node (ref "IC2") (pin "37") (pinfunction "D14_37") (pintype "bidirectional"))
    )
    (net (code "46") (name "D15") (class "Default")
      (node (ref "IC1") (pin "52") (pinfunction "IOR_53_52") (pintype "bidirectional"))
      (node (ref "IC2") (pin "38") (pinfunction "D15_38") (pintype "bidirectional"))
    )
    (net (code "47") (name "GND") (class "Default")
      (node (ref "C1") (pin "2") (pinfunction "2_2") (pintype "passive"))
      (node (ref "C10") (pin "2") (pinfunction "2_2") (pintype "passive"))
      (node (ref "C11") (pin "2") (pinfunction "2_2") (pintype "passive"))
      (node (ref "C12") (pin "2") (pinfunction "2_2") (pintype "passive"))
      (node (ref "C13") (pin "2") (pinfunction "2_2") (pintype "passive"))
      (node (ref "C14") (pin "2") (pinfunction "2_2") (pintype "passive"))
      (node (ref "C15") (pin "2") (pinfunction "2_2") (pintype "passive"))
      (node (ref "C16") (pin "2") (pinfunction "2_2") (pintype "passive"))
      (node (ref "C18") (pin "2") (pinfunction "2_2") (pintype "passive"))
      (node (ref "C19") (pin "2") (pinfunction "2_2") (pintype "passive"))
      (node (ref "C2") (pin "2") (pinfunction "2_2") (pintype "passive"))
      (node (ref "C20") (pin "2") (pinfunction "2_2") (pintype "passive"))
      (node (ref "C21") (pin "2") (pinfunction "2_2") (pintype "passive"))
      (node (ref "C22") (pin "2") (pinfunction "2_2") (pintype "passive"))
      (node (ref "C24") (pin "2") (pinfunction "2_2") (pintype "passive"))
      (node (ref "C26") (pin "2") (pinfunction "2_2") (pintype "passive"))
      (node (ref "C27") (pin "2") (pinfunction "2_2") (pintype "passive"))
      (node (ref "C3") (pin "2") (pinfunction "2_2") (pintype "passive"))
      (node (ref "C34") (pin "2") (pinfunction "2_2") (pintype "passive"))
      (node (ref "C35") (pin "2") (pinfunction "2_2") (pintype "passive"))
      (node (ref "C36") (pin "2") (pinfunction "2_2") (pintype "passive"))
      (node (ref "C37") (pin "2") (pinfunction "2_2") (pintype "passive"))
      (node (ref "C38") (pin "2") (pinfunction "2_2") (pintype "passive"))
      (node (ref "C39") (pin "2") (pinfunction "2_2") (pintype "passive"))
      (node (ref "C4") (pin "2") (pinfunction "2_2") (pintype "passive"))
      (node (ref "C40") (pin "2") (pinfunction "2_2") (pintype "passive"))
      (node (ref "C41") (pin "2") (pinfunction "2_2") (pintype "passive"))
      (node (ref "C42") (pin "2") (pinfunction "2_2") (pintype "passive"))
      (node (ref "C43") (pin "2") (pinfunction "2_2") (pintype "passive"))
      (node (ref "C44") (pin "2") (pinfunction "2_2") (pintype "passive"))
      (node (ref "C47") (pin "2") (pinfunction "2_2") (pintype "passive"))
      (node (ref "C48") (pin "1") (pinfunction "1_1") (pintype "passive"))
      (node (ref "C49") (pin "1") (pinfunction "1_1") (pintype "passive"))
      (node (ref "C5") (pin "2") (pinfunction "2_2") (pintype "passive"))
      (node (ref "C50") (pin "2") (pinfunction "2_2") (pintype "passive"))
      (node (ref "C6") (pin "2") (pinfunction "2_2") (pintype "passive"))
      (node (ref "C7") (pin "2") (pinfunction "2_2") (pintype "passive"))
      (node (ref "C8") (pin "2") (pinfunction "2_2") (pintype "passive"))
      (node (ref "C9") (pin "2") (pinfunction "2_2") (pintype "passive"))
      (node (ref "IC1") (pin "17") (pinfunction "GND_17") (pintype "bidirectional"))
      (node (ref "IC1") (pin "23") (pinfunction "GND_23") (pintype "bidirectional"))
      (node (ref "IC1") (pin "32") (pinfunction "GND_32") (pintype "bidirectional"))
      (node (ref "IC1") (pin "39") (pinfunction "GND_39") (pintype "bidirectional"))
      (node (ref "IC1") (pin "47") (pinfunction "GND_47") (pintype "bidirectional"))
      (node (ref "IC1") (pin "5") (pinfunction "GND_5") (pintype "bidirectional"))
      (node (ref "IC1") (pin "55") (pinfunction "GND_55") (pintype "bidirectional"))
      (node (ref "IC1") (pin "70") (pinfunction "GND_70") (pintype "bidirectional"))
      (node (ref "IC1") (pin "84") (pinfunction "GND_84") (pintype "bidirectional"))
      (node (ref "IC1") (pin "98") (pinfunction "GND_98") (pintype "bidirectional"))
      (node (ref "IC2") (pin "12") (pinfunction "GND_12") (pintype "bidirectional"))
      (node (ref "IC2") (pin "34") (pinfunction "GND_34") (pintype "bidirectional"))
      (node (ref "IC2") (pin "39") (pinfunction "~{LB}_39") (pintype "bidirectional"))
      (node (ref "IC2") (pin "40") (pinfunction "~{UB}_40") (pintype "bidirectional"))
      (node (ref "IC3") (pin "4") (pinfunction "GND_4") (pintype "bidirectional"))
      (node (ref "IC4") (pin "P$6") (pinfunction "DGND_P$6") (pintype "bidirectional"))
      (node (ref "IC4") (pin "P$8") (pinfunction "AGND1_P$8") (pintype "bidirectional"))
      (node (ref "IC4") (pin "P32") (pinfunction "PGND2_P32") (pintype "bidirectional"))
      (node (ref "IC4") (pin "P41") (pinfunction "PGND1_P41") (pintype "bidirectional"))
      (node (ref "IC4") (pin "P48") (pinfunction "AGND2_P48") (pintype "bidirectional"))
      (node (ref "IC5") (pin "2") (pinfunction "GND_2") (pintype "bidirectional"))
      (node (ref "IC6") (pin "2") (pinfunction "GND_2") (pintype "bidirectional"))
      (node (ref "J1") (pin "31") (pinfunction "31_31") (pintype "passive"))
      (node (ref "J1") (pin "32") (pinfunction "32_32") (pintype "passive"))
      (node (ref "J1") (pin "5") (pinfunction "5_5") (pintype "passive"))
      (node (ref "J1") (pin "7") (pinfunction "7_7") (pintype "passive"))
      (node (ref "J1") (pin "P$1") (pinfunction "SHIELD_P$1") (pintype "bidirectional"))
      (node (ref "J1") (pin "P$2") (pinfunction "SHIELD_P$2") (pintype "bidirectional"))
      (node (ref "J1") (pin "P$3") (pinfunction "SHIELD_P$3") (pintype "bidirectional"))
      (node (ref "J1") (pin "P$4") (pinfunction "SHIELD_P$4") (pintype "bidirectional"))
      (node (ref "J2") (pin "15") (pinfunction "15_15") (pintype "passive"))
      (node (ref "L4") (pin "P$2") (pinfunction "P$2_P$2") (pintype "bidirectional"))
      (node (ref "NTC1") (pin "1") (pinfunction "1_1") (pintype "passive"))
      (node (ref "R12") (pin "1") (pinfunction "1_1") (pintype "passive"))
      (node (ref "R14") (pin "2") (pinfunction "2_2") (pintype "passive"))
      (node (ref "R19") (pin "1") (pinfunction "1_1") (pintype "passive"))
      (node (ref "R21") (pin "1") (pinfunction "1_1") (pintype "passive"))
      (node (ref "R7") (pin "1") (pinfunction "1_1") (pintype "passive"))
      (node (ref "R9") (pin "1") (pinfunction "1_1") (pintype "passive"))
      (node (ref "SV1") (pin "7") (pinfunction "7_7") (pintype "passive"))
      (node (ref "X1") (pin "2") (pinfunction "2_2") (pintype "bidirectional"))
    )
    (net (code "48") (name "INT_PIN") (class "Default")
      (node (ref "IC4") (pin "P$2") (pinfunction "INT_N_P$2") (pintype "bidirectional"))
      (node (ref "J2") (pin "8") (pinfunction "8_8") (pintype "passive"))
    )
    (net (code "49") (name "LCD_CKV") (class "Default")
      (node (ref "IC1") (pin "42") (pinfunction "IOB_43_CBSEL1_42") (pintype "bidirectional"))
      (node (ref "J1") (pin "27") (pinfunction "27_27") (pintype "passive"))
    )
    (net (code "50") (name "LCD_CL") (class "Default")
      (node (ref "IC1") (pin "21") (pinfunction "IOL_10B_21") (pintype "bidirectional"))
      (node (ref "J1") (pin "10") (pinfunction "10_10") (pintype "passive"))
    )
    (net (code "51") (name "LCD_D0") (class "Default")
      (node (ref "IC1") (pin "27") (pinfunction "IOB_27_27") (pintype "bidirectional"))
      (node (ref "J1") (pin "14") (pinfunction "14_14") (pintype "passive"))
    )
    (net (code "52") (name "LCD_D1") (class "Default")
      (node (ref "IC1") (pin "28") (pinfunction "IOB_28_28") (pintype "bidirectional"))
      (node (ref "J1") (pin "13") (pinfunction "13_13") (pintype "passive"))
    )
    (net (code "53") (name "LCD_D2") (class "Default")
      (node (ref "IC1") (pin "29") (pinfunction "IOB_29_29") (pintype "bidirectional"))
      (node (ref "J1") (pin "16") (pinfunction "16_16") (pintype "passive"))
    )
    (net (code "54") (name "LCD_D3") (class "Default")
      (node (ref "IC1") (pin "30") (pinfunction "IOB_30_30") (pintype "bidirectional"))
      (node (ref "J1") (pin "15") (pinfunction "15_15") (pintype "passive"))
    )
    (net (code "55") (name "LCD_D4") (class "Default")
      (node (ref "IC1") (pin "33") (pinfunction "IOB_35_GBIN5_33") (pintype "bidirectional"))
      (node (ref "J1") (pin "18") (pinfunction "18_18") (pintype "passive"))
    )
    (net (code "56") (name "LCD_D5") (class "Default")
      (node (ref "IC1") (pin "34") (pinfunction "IOB_36_GBIN4_34") (pintype "bidirectional"))
      (node (ref "J1") (pin "17") (pinfunction "17_17") (pintype "passive"))
    )
    (net (code "57") (name "LCD_D6") (class "Default")
      (node (ref "IC1") (pin "36") (pinfunction "IOB_34_36") (pintype "bidirectional"))
      (node (ref "J1") (pin "20") (pinfunction "20_20") (pintype "passive"))
    )
    (net (code "58") (name "LCD_D7") (class "Default")
      (node (ref "IC1") (pin "37") (pinfunction "IOB_37_37") (pintype "bidirectional"))
      (node (ref "J1") (pin "19") (pinfunction "19_19") (pintype "passive"))
    )
    (net (code "59") (name "LCD_GMODE") (class "Default")
      (node (ref "IC1") (pin "40") (pinfunction "IOB_41_40") (pintype "bidirectional"))
      (node (ref "J1") (pin "25") (pinfunction "25_25") (pintype "passive"))
    )
    (net (code "60") (name "LCD_GVDD") (class "Default")
      (node (ref "D11") (pin "C") (pinfunction "C_C") (pintype "bidirectional"))
      (node (ref "J1") (pin "26") (pinfunction "26_26") (pintype "passive"))
      (node (ref "R13") (pin "1") (pinfunction "1_1") (pintype "passive"))
      (node (ref "R15") (pin "2") (pinfunction "2_2") (pintype "passive"))
    )
    (net (code "61") (name "LCD_GVEE") (class "Default")
      (node (ref "D13") (pin "A") (pinfunction "A_A") (pintype "bidirectional"))
      (node (ref "J1") (pin "28") (pinfunction "28_28") (pintype "passive"))
      (node (ref "J1") (pin "30") (pinfunction "30_30") (pintype "passive"))
      (node (ref "R11") (pin "2") (pinfunction "2_2") (pintype "passive"))
      (node (ref "R20") (pin "2") (pinfunction "2_2") (pintype "passive"))
    )
    (net (code "62") (name "LCD_LE") (class "Default")
      (node (ref "IC1") (pin "24") (pinfunction "IOL_12A_24") (pintype "bidirectional"))
      (node (ref "J1") (pin "9") (pinfunction "9_9") (pintype "passive"))
    )
    (net (code "63") (name "LCD_OE") (class "Default")
      (node (ref "IC1") (pin "25") (pinfunction "IOL_12B_25") (pintype "bidirectional"))
      (node (ref "J1") (pin "12") (pinfunction "12_12") (pintype "passive"))
    )
    (net (code "64") (name "LCD_SPH") (class "Default")
      (node (ref "IC1") (pin "26") (pinfunction "IOB_26_26") (pintype "bidirectional"))
      (node (ref "J1") (pin "11") (pinfunction "11_11") (pintype "passive"))
    )
    (net (code "65") (name "LCD_SPV") (class "Default")
      (node (ref "IC1") (pin "41") (pinfunction "IOB_42_CBSEL0_41") (pintype "bidirectional"))
      (node (ref "J1") (pin "29") (pinfunction "29_29") (pintype "passive"))
    )
    (net (code "66") (name "LCD_VCOM") (class "Default")
      (node (ref "C47") (pin "1") (pinfunction "1_1") (pintype "passive"))
      (node (ref "IC4") (pin "P15") (pinfunction "VCOM_P15") (pintype "bidirectional"))
      (node (ref "J1") (pin "22") (pinfunction "22_22") (pintype "passive"))
      (node (ref "J1") (pin "24") (pinfunction "24_24") (pintype "passive"))
      (node (ref "R17") (pin "2") (pinfunction "2_2") (pintype "passive"))
    )
    (net (code "67") (name "LCD_VNEG") (class "Default")
      (node (ref "C43") (pin "1") (pinfunction "1_1") (pintype "passive"))
      (node (ref "IC4") (pin "P$3") (pinfunction "VNEG_P$3") (pintype "bidirectional"))
      (node (ref "J1") (pin "2") (pinfunction "2_2") (pintype "passive"))
      (node (ref "J1") (pin "4") (pinfunction "4_4") (pintype "passive"))
      (node (ref "R16") (pin "2") (pinfunction "2_2") (pintype "passive"))
    )
    (net (code "68") (name "LCD_VPOS") (class "Default")
      (node (ref "C48") (pin "2") (pinfunction "2_2") (pintype "passive"))
      (node (ref "IC4") (pin "P44") (pinfunction "VPOS_P44") (pintype "bidirectional"))
      (node (ref "J1") (pin "1") (pinfunction "1_1") (pintype "passive"))
      (node (ref "J1") (pin "3") (pinfunction "3_3") (pintype "passive"))
      (node (ref "R18") (pin "2") (pinfunction "2_2") (pintype "passive"))
    )
    (net (code "69") (name "Net-(C45-Pad2)") (class "Default")
      (node (ref "C45") (pin "2") (pinfunction "2_2") (pintype "passive"))
      (node (ref "D12") (pin "A") (pinfunction "A_A") (pintype "bidirectional"))
      (node (ref "D13") (pin "C") (pinfunction "C_C") (pintype "bidirectional"))
    )
    (net (code "70") (name "Net-(C46-Pad1)") (class "Default")
      (node (ref "C46") (pin "1") (pinfunction "1_1") (pintype "passive"))
      (node (ref "D10") (pin "C") (pinfunction "C_C") (pintype "bidirectional"))
      (node (ref "D11") (pin "A") (pinfunction "A_A") (pintype "bidirectional"))
    )
    (net (code "71") (name "Net-(IC3-CE#)") (class "Default")
      (node (ref "IC3") (pin "1") (pinfunction "CE#_1") (pintype "bidirectional"))
      (node (ref "R2") (pin "2") (pinfunction "2_2") (pintype "passive"))
      (node (ref "R3") (pin "1") (pinfunction "1_1") (pintype "passive"))
    )
    (net (code "72") (name "Net-(IC3-HOLD#)") (class "Default")
      (node (ref "IC3") (pin "3") (pinfunction "WP#_3") (pintype "bidirectional"))
      (node (ref "IC3") (pin "7") (pinfunction "HOLD#_7") (pintype "bidirectional"))
      (node (ref "R1") (pin "1") (pinfunction "1_1") (pintype "passive"))
    )
    (net (code "73") (name "Net-(IC4-INT_LDO)") (class "Default")
      (node (ref "C39") (pin "1") (pinfunction "1_1") (pintype "passive"))
      (node (ref "IC4") (pin "P$7") (pinfunction "INT_LDO_P$7") (pintype "bidirectional"))
    )
    (net (code "74") (name "Net-(IC4-TS)") (class "Default")
      (node (ref "IC4") (pin "P47") (pinfunction "TS_P47") (pintype "bidirectional"))
      (node (ref "NTC1") (pin "2") (pinfunction "2_2") (pintype "passive"))
      (node (ref "R19") (pin "2") (pinfunction "2_2") (pintype "passive"))
    )
    (net (code "75") (name "Net-(IC4-VB_SW)") (class "Default")
      (node (ref "D8") (pin "A") (pinfunction "A_A") (pintype "bidirectional"))
      (node (ref "IC4") (pin "P40") (pinfunction "VB_SW_P40") (pintype "bidirectional"))
      (node (ref "L3") (pin "P$2") (pinfunction "P$2_P$2") (pintype "bidirectional"))
    )
    (net (code "76") (name "Net-(IC4-VCOM_DIS)") (class "Default")
      (node (ref "IC4") (pin "P14") (pinfunction "VCOM_DIS_P14") (pintype "bidirectional"))
      (node (ref "R17") (pin "1") (pinfunction "1_1") (pintype "passive"))
    )
    (net (code "77") (name "Net-(IC4-VDDH_D)") (class "Default")
      (node (ref "C49") (pin "2") (pinfunction "2_2") (pintype "passive"))
      (node (ref "D10") (pin "A") (pinfunction "A_A") (pintype "bidirectional"))
      (node (ref "IC4") (pin "P34") (pinfunction "VDDH_D_P34") (pintype "bidirectional"))
    )
    (net (code "78") (name "Net-(IC4-VDDH_DIS)") (class "Default")
      (node (ref "IC4") (pin "P35") (pinfunction "VDDH_DIS_P35") (pintype "bidirectional"))
      (node (ref "R15") (pin "1") (pinfunction "1_1") (pintype "passive"))
    )
    (net (code "79") (name "Net-(IC4-VDDH_DRV)") (class "Default")
      (node (ref "C46") (pin "2") (pinfunction "2_2") (pintype "passive"))
      (node (ref "IC4") (pin "P36") (pinfunction "VDDH_DRV_P36") (pintype "bidirectional"))
    )
    (net (code "80") (name "Net-(IC4-VDDH_FB)") (class "Default")
      (node (ref "IC4") (pin "P33") (pinfunction "VDDH_FB_P33") (pintype "bidirectional"))
      (node (ref "R13") (pin "2") (pinfunction "2_2") (pintype "passive"))
      (node (ref "R14") (pin "1") (pinfunction "1_1") (pintype "passive"))
    )
    (net (code "81") (name "Net-(IC4-VEE_D)") (class "Default")
      (node (ref "C50") (pin "1") (pinfunction "1_1") (pintype "passive"))
      (node (ref "D12") (pin "C") (pinfunction "C_C") (pintype "bidirectional"))
      (node (ref "IC4") (pin "P30") (pinfunction "VEE_D_P30") (pintype "bidirectional"))
    )
    (net (code "82") (name "Net-(IC4-VEE_DIS)") (class "Default")
      (node (ref "IC4") (pin "P29") (pinfunction "VEE_DIS_P29") (pintype "bidirectional"))
      (node (ref "R20") (pin "1") (pinfunction "1_1") (pintype "passive"))
    )
    (net (code "83") (name "Net-(IC4-VEE_DRV)") (class "Default")
      (node (ref "C45") (pin "1") (pinfunction "1_1") (pintype "passive"))
      (node (ref "IC4") (pin "P28") (pinfunction "VEE_DRV_P28") (pintype "bidirectional"))
    )
    (net (code "84") (name "Net-(IC4-VEE_FB)") (class "Default")
      (node (ref "IC4") (pin "P31") (pinfunction "VEE_FB_P31") (pintype "bidirectional"))
      (node (ref "R11") (pin "1") (pinfunction "1_1") (pintype "passive"))
      (node (ref "R12") (pin "2") (pinfunction "2_2") (pintype "passive"))
    )
    (net (code "85") (name "Net-(IC4-VNEG_DIS)") (class "Default")
      (node (ref "IC4") (pin "P$9") (pinfunction "VNEG_DIS_P$9") (pintype "bidirectional"))
      (node (ref "R16") (pin "1") (pinfunction "1_1") (pintype "passive"))
    )
    (net (code "86") (name "Net-(IC4-VN_SW)") (class "Default")
      (node (ref "D9") (pin "C") (pinfunction "C_C") (pintype "bidirectional"))
      (node (ref "IC4") (pin "P25") (pinfunction "VN_SW_P25") (pintype "bidirectional"))
      (node (ref "L4") (pin "P$1") (pinfunction "P$1_P$1") (pintype "bidirectional"))
    )
    (net (code "87") (name "Net-(IC4-VPOS_DIS)") (class "Default")
      (node (ref "IC4") (pin "P19") (pinfunction "VPOS_DIS_P19") (pintype "bidirectional"))
      (node (ref "R18") (pin "1") (pinfunction "1_1") (pintype "passive"))
    )
    (net (code "88") (name "Net-(IC4-VREF)") (class "Default")
      (node (ref "C44") (pin "1") (pinfunction "1_1") (pintype "passive"))
      (node (ref "IC4") (pin "P$1") (pinfunction "VREF_P$1") (pintype "bidirectional"))
    )
    (net (code "89") (name "Net-(IC5-FB)") (class "Default")
      (node (ref "C17") (pin "1") (pinfunction "1_1") (pintype "passive"))
      (node (ref "IC5") (pin "5") (pinfunction "FB_5") (pintype "bidirectional"))
      (node (ref "R8") (pin "2") (pinfunction "2_2") (pintype "passive"))
      (node (ref "R9") (pin "2") (pinfunction "2_2") (pintype "passive"))
    )
    (net (code "90") (name "Net-(IC5-SW)") (class "Default")
      (node (ref "IC5") (pin "3") (pinfunction "SW_3") (pintype "bidirectional"))
      (node (ref "L1") (pin "P$1") (pinfunction "P$1_P$1") (pintype "bidirectional"))
    )
    (net (code "91") (name "Net-(IC6-FB)") (class "Default")
      (node (ref "C23") (pin "1") (pinfunction "1_1") (pintype "passive"))
      (node (ref "IC6") (pin "5") (pinfunction "FB_5") (pintype "bidirectional"))
      (node (ref "R10") (pin "2") (pinfunction "2_2") (pintype "passive"))
      (node (ref "R21") (pin "2") (pinfunction "2_2") (pintype "passive"))
    )
    (net (code "92") (name "Net-(IC6-SW)") (class "Default")
      (node (ref "IC6") (pin "3") (pinfunction "SW_3") (pintype "bidirectional"))
      (node (ref "L2") (pin "P$1") (pinfunction "P$1_P$1") (pintype "bidirectional"))
    )
    (net (code "93") (name "Net-(LED1-PadC)") (class "Default")
      (node (ref "LED1") (pin "C") (pinfunction "C_C") (pintype "passive"))
      (node (ref "R7") (pin "2") (pinfunction "2_2") (pintype "passive"))
    )
    (net (code "94") (name "Net-(LED2-PadA)") (class "Default")
      (node (ref "LED2") (pin "A") (pinfunction "A_A") (pintype "passive"))
      (node (ref "R22") (pin "2") (pinfunction "2_2") (pintype "passive"))
    )
    (net (code "95") (name "PG_PIN") (class "Default")
      (node (ref "IC4") (pin "P23") (pinfunction "PWR_GOOD_P23") (pintype "bidirectional"))
      (node (ref "LED2") (pin "C") (pinfunction "C_C") (pintype "passive"))
    )
    (net (code "96") (name "SCL_PIN") (class "Default")
      (node (ref "IC4") (pin "P17") (pinfunction "SCL_P17") (pintype "bidirectional"))
      (node (ref "J2") (pin "11") (pinfunction "11_11") (pintype "passive"))
    )
    (net (code "97") (name "SDA_PIN") (class "Default")
      (node (ref "IC4") (pin "P18") (pinfunction "SDA_P18") (pintype "bidirectional"))
      (node (ref "J2") (pin "12") (pinfunction "12_12") (pintype "passive"))
    )
    (net (code "98") (name "SPI_CLK") (class "Default")
      (node (ref "IC1") (pin "1") (pinfunction "IOL_1A_1") (pintype "bidirectional"))
      (node (ref "J2") (pin "1") (pinfunction "1_1") (pintype "passive"))
    )
    (net (code "99") (name "SPI_CMD") (class "Default")
      (node (ref "IC1") (pin "8") (pinfunction "IOL_3B_8") (pintype "bidirectional"))
      (node (ref "J2") (pin "7") (pinfunction "7_7") (pintype "passive"))
    )
    (net (code "100") (name "SPI_CS") (class "Default")
      (node (ref "IC1") (pin "9") (pinfunction "IOL_5A_9") (pintype "bidirectional"))
      (node (ref "J2") (pin "6") (pinfunction "6_6") (pintype "passive"))
    )
    (net (code "101") (name "SPI_DATA0") (class "Default")
      (node (ref "IC1") (pin "2") (pinfunction "IOL_1B_2") (pintype "bidirectional"))
      (node (ref "J2") (pin "2") (pinfunction "2_2") (pintype "passive"))
    )
    (net (code "102") (name "SPI_DATA1") (class "Default")
      (node (ref "IC1") (pin "3") (pinfunction "IOL_2A_3") (pintype "bidirectional"))
      (node (ref "J2") (pin "3") (pinfunction "3_3") (pintype "passive"))
    )
    (net (code "103") (name "SPI_DATA2") (class "Default")
      (node (ref "IC1") (pin "4") (pinfunction "IOL_2B_4") (pintype "bidirectional"))
      (node (ref "J2") (pin "4") (pinfunction "4_4") (pintype "passive"))
    )
    (net (code "104") (name "SPI_DATA3") (class "Default")
      (node (ref "IC1") (pin "7") (pinfunction "IOL_3A_7") (pintype "bidirectional"))
      (node (ref "J2") (pin "5") (pinfunction "5_5") (pintype "passive"))
    )
    (net (code "105") (name "VB") (class "Default")
      (node (ref "C35") (pin "1") (pinfunction "1_1") (pintype "passive"))
      (node (ref "C36") (pin "1") (pinfunction "1_1") (pintype "passive"))
      (node (ref "D8") (pin "C") (pinfunction "C_C") (pintype "bidirectional"))
      (node (ref "IC4") (pin "P37") (pinfunction "VDDH_IN_P37") (pintype "bidirectional"))
      (node (ref "IC4") (pin "P42") (pinfunction "VB_P42") (pintype "bidirectional"))
      (node (ref "IC4") (pin "P43") (pinfunction "VPOS_IN_P43") (pintype "bidirectional"))
    )
    (net (code "106") (name "VIN") (class "Default")
      (node (ref "C21") (pin "1") (pinfunction "1_1") (pintype "passive"))
      (node (ref "C24") (pin "1") (pinfunction "1_1") (pintype "passive"))
      (node (ref "IC5") (pin "1") (pinfunction "EN_1") (pintype "bidirectional"))
      (node (ref "IC5") (pin "4") (pinfunction "VIN_4") (pintype "bidirectional"))
      (node (ref "IC6") (pin "1") (pinfunction "EN_1") (pintype "bidirectional"))
      (node (ref "IC6") (pin "4") (pinfunction "VIN_4") (pintype "bidirectional"))
      (node (ref "J2") (pin "14") (pinfunction "14_14") (pintype "passive"))
    )
    (net (code "107") (name "VN") (class "Default")
      (node (ref "C37") (pin "1") (pinfunction "1_1") (pintype "passive"))
      (node (ref "C41") (pin "1") (pinfunction "1_1") (pintype "passive"))
      (node (ref "C42") (pin "1") (pinfunction "1_1") (pintype "passive"))
      (node (ref "D9") (pin "A") (pinfunction "A_A") (pintype "bidirectional"))
      (node (ref "IC4") (pin "GN0") (pinfunction "POWER_PAD_GN0") (pintype "bidirectional"))
      (node (ref "IC4") (pin "GN1") (pinfunction "POWER_PAD_GN1") (pintype "bidirectional"))
      (node (ref "IC4") (pin "GN10") (pinfunction "POWER_PAD_GN10") (pintype "bidirectional"))
      (node (ref "IC4") (pin "GN11") (pinfunction "POWER_PAD_GN11") (pintype "bidirectional"))
      (node (ref "IC4") (pin "GN12") (pinfunction "POWER_PAD_GN12") (pintype "bidirectional"))
      (node (ref "IC4") (pin "GN13") (pinfunction "POWER_PAD_GN13") (pintype "bidirectional"))
      (node (ref "IC4") (pin "GN14") (pinfunction "POWER_PAD_GN14") (pintype "bidirectional"))
      (node (ref "IC4") (pin "GN15") (pinfunction "POWER_PAD_GN15") (pintype "bidirectional"))
      (node (ref "IC4") (pin "GN16") (pinfunction "POWER_PAD_GN16") (pintype "bidirectional"))
      (node (ref "IC4") (pin "GN2") (pinfunction "POWER_PAD_GN2") (pintype "bidirectional"))
      (node (ref "IC4") (pin "GN3") (pinfunction "POWER_PAD_GN3") (pintype "bidirectional"))
      (node (ref "IC4") (pin "GN4") (pinfunction "POWER_PAD_GN4") (pintype "bidirectional"))
      (node (ref "IC4") (pin "GN5") (pinfunction "POWER_PAD_GN5") (pintype "bidirectional"))
      (node (ref "IC4") (pin "GN6") (pinfunction "POWER_PAD_GN6") (pintype "bidirectional"))
      (node (ref "IC4") (pin "GN7") (pinfunction "POWER_PAD_GN7") (pintype "bidirectional"))
      (node (ref "IC4") (pin "GN8") (pinfunction "POWER_PAD_GN8") (pintype "bidirectional"))
      (node (ref "IC4") (pin "GN9") (pinfunction "POWER_PAD_GN9") (pintype "bidirectional"))
      (node (ref "IC4") (pin "P$4") (pinfunction "VNEG_IN_P$4") (pintype "bidirectional"))
      (node (ref "IC4") (pin "P16") (pinfunction "VCOM_PWR_P16") (pintype "bidirectional"))
      (node (ref "IC4") (pin "P22") (pinfunction "PBKG_P22") (pintype "bidirectional"))
      (node (ref "IC4") (pin "P26") (pinfunction "VN_P26") (pintype "bidirectional"))
      (node (ref "IC4") (pin "P27") (pinfunction "VEE_IN_P27") (pintype "bidirectional"))
    )
    (net (code "108") (name "WAKE_PIN") (class "Default")
      (node (ref "IC4") (pin "P$5") (pinfunction "WAKEUP_P$5") (pintype "bidirectional"))
      (node (ref "J2") (pin "9") (pinfunction "9_9") (pintype "passive"))
    )
    (net (code "109") (name "unconnected-(IC1-IOL_5B-Pad10)") (class "Default")
      (node (ref "IC1") (pin "10") (pinfunction "IOL_5B_10") (pintype "bidirectional"))
    )
    (net (code "110") (name "unconnected-(IC1-IOL_6A-Pad12)") (class "Default")
      (node (ref "IC1") (pin "12") (pinfunction "IOL_6A_12") (pintype "bidirectional"))
    )
    (net (code "111") (name "unconnected-(IC1-IOL_6B_GBIN7-Pad13)") (class "Default")
      (node (ref "IC1") (pin "13") (pinfunction "IOL_6B_GBIN7_13") (pintype "bidirectional"))
    )
    (net (code "112") (name "unconnected-(IC1-IOL_7B-Pad16)") (class "Default")
      (node (ref "IC1") (pin "16") (pinfunction "IOL_7B_16") (pintype "bidirectional"))
    )
    (net (code "113") (name "unconnected-(IC1-IOL_8A-Pad18)") (class "Default")
      (node (ref "IC1") (pin "18") (pinfunction "IOL_8A_18") (pintype "bidirectional"))
    )
    (net (code "114") (name "unconnected-(IC1-IOL_8B-Pad19)") (class "Default")
      (node (ref "IC1") (pin "19") (pinfunction "IOL_8B_19") (pintype "bidirectional"))
    )
    (net (code "115") (name "unconnected-(IC1-IOL_10A-Pad20)") (class "Default")
      (node (ref "IC1") (pin "20") (pinfunction "IOL_10A_20") (pintype "bidirectional"))
    )
    (net (code "116") (name "unconnected-(IC1-VPP_FAST-Pad76)") (class "Default")
      (node (ref "IC1") (pin "76") (pinfunction "VPP_FAST_76") (pintype "bidirectional"))
    )
    (net (code "117") (name "unconnected-(IC4-V3P3-PadP46)") (class "Default")
      (node (ref "IC4") (pin "P46") (pinfunction "V3P3_P46") (pintype "bidirectional"))
    )
    (net (code "118") (name "unconnected-(J1-Pad21)") (class "Default")
      (node (ref "J1") (pin "21") (pinfunction "21_21") (pintype "passive"))
    )
    (net (code "119") (name "unconnected-(J1-Pad23)") (class "Default")
      (node (ref "J1") (pin "23") (pinfunction "23_23") (pintype "passive"))
    )
    (net (code "120") (name "unconnected-(J1-Pad33)") (class "Default")
      (node (ref "J1") (pin "33") (pinfunction "33_33") (pintype "passive"))
    )
    (net (code "121") (name "unconnected-(J1-Pad34)") (class "Default")
      (node (ref "J1") (pin "34") (pinfunction "34_34") (pintype "passive"))
    )
    (net (code "122") (name "unconnected-(X1-Pad1)") (class "Default")
      (node (ref "X1") (pin "1") (pinfunction "1_1") (pintype "bidirectional"))
    )
    (net (code "123") (name "~{CE}") (class "Default")
      (node (ref "IC1") (pin "54") (pinfunction "IOR_55_54") (pintype "bidirectional"))
      (node (ref "IC2") (pin "6") (pinfunction "~{CE}_6") (pintype "bidirectional"))
      (node (ref "R4") (pin "2") (pinfunction "2_2") (pintype "passive"))
    )
    (net (code "124") (name "~{OE}") (class "Default")
      (node (ref "IC1") (pin "51") (pinfunction "IOR_52_51") (pintype "bidirectional"))
      (node (ref "IC2") (pin "41") (pinfunction "~{OE}_41") (pintype "bidirectional"))
    )
    (net (code "125") (name "~{WE}") (class "Default")
      (node (ref "IC1") (pin "74") (pinfunction "IOR_72_74") (pintype "bidirectional"))
      (node (ref "IC2") (pin "17") (pinfunction "~{WE}_17") (pintype "bidirectional"))
    )
  )
)
